# GR.net
KiCad netlist of a schematic drawn in Altium Designer
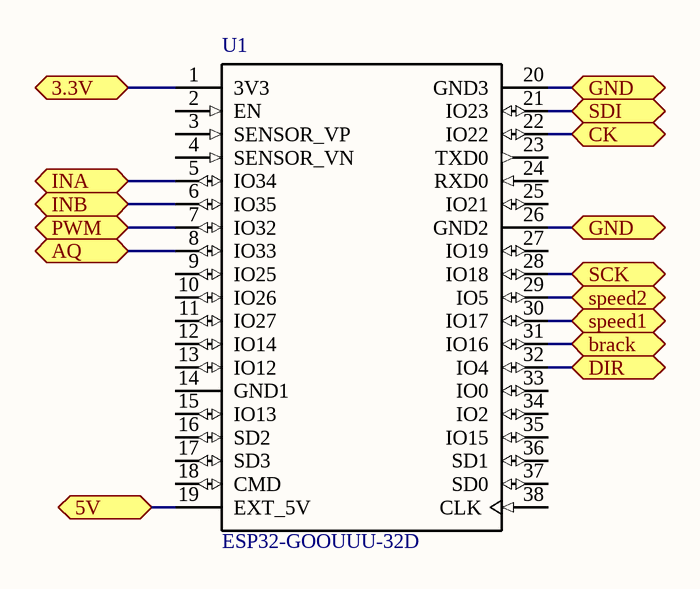
[diagram p0: GR.SchDoc]

(export (version "E")
  (design (tool "Eeschema 10.0.6"))
  (components
    (comp (ref "U1")
      (value "ESP32-GOOUUU-32D")
      (footprint "ESP32-GOOUUU-32D")
      (description "Eval Board For Esp-Wroom-32")
      (fields (field (name "MP") "ESP32-DEVKITC-32D") (field (name "MF") "Espressif Systems"))
      (libsource (lib "ESP32-GOOUUU-32D") (part "ESP32-GOOUUU-32D"))
    )
  )
  (nets
    (net (code "1") (name "/3.3V") (class "Default")
      (node (ref "U1") (pin "1") (pinfunction "3V3_1") (pintype "power_in"))
    )
    (net (code "2") (name "/5V") (class "Default")
      (node (ref "U1") (pin "19") (pinfunction "EXT_5V_19") (pintype "power_in"))
    )
    (net (code "3") (name "/AQ") (class "Default")
      (node (ref "U1") (pin "8") (pinfunction "IO33_8") (pintype "bidirectional"))
    )
    (net (code "4") (name "/CK") (class "Default")
      (node (ref "U1") (pin "22") (pinfunction "IO22_22") (pintype "bidirectional"))
    )
    (net (code "5") (name "/DIR") (class "Default")
      (node (ref "U1") (pin "32") (pinfunction "IO4_32") (pintype "bidirectional"))
    )
    (net (code "6") (name "/GND") (class "Default")
      (node (ref "U1") (pin "20") (pinfunction "GND3_20") (pintype "power_in"))
      (node (ref "U1") (pin "26") (pinfunction "GND2_26") (pintype "power_in"))
    )
    (net (code "7") (name "/INA") (class "Default")
      (node (ref "U1") (pin "5") (pinfunction "IO34_5") (pintype "bidirectional"))
    )
    (net (code "8") (name "/INB") (class "Default")
      (node (ref "U1") (pin "6") (pinfunction "IO35_6") (pintype "bidirectional"))
    )
    (net (code "9") (name "/PWM") (class "Default")
      (node (ref "U1") (pin "7") (pinfunction "IO32_7") (pintype "bidirectional"))
    )
    (net (code "10") (name "/SCK") (class "Default")
      (node (ref "U1") (pin "28") (pinfunction "IO18_28") (pintype "bidirectional"))
    )
    (net (code "11") (name "/SDI") (class "Default")
      (node (ref "U1") (pin "21") (pinfunction "IO23_21") (pintype "bidirectional"))
    )
    (net (code "12") (name "/brack") (class "Default")
      (node (ref "U1") (pin "31") (pinfunction "IO16_31") (pintype "bidirectional"))
    )
    (net (code "13") (name "/speed1") (class "Default")
      (node (ref "U1") (pin "30") (pinfunction "IO17_30") (pintype "bidirectional"))
    )
    (net (code "14") (name "/speed2") (class "Default")
      (node (ref "U1") (pin "29") (pinfunction "IO5_29") (pintype "bidirectional"))
    )
    (net (code "15") (name "unconnected-(U1-CLK-Pad38)") (class "Default")
      (node (ref "U1") (pin "38") (pinfunction "CLK_38") (pintype "input"))
    )
    (net (code "16") (name "unconnected-(U1-CMD-Pad18)") (class "Default")
      (node (ref "U1") (pin "18") (pinfunction "CMD_18") (pintype "bidirectional"))
    )
    (net (code "17") (name "unconnected-(U1-EN-Pad2)") (class "Default")
      (node (ref "U1") (pin "2") (pinfunction "EN_2") (pintype "input"))
    )
    (net (code "18") (name "unconnected-(U1-GND1-Pad14)") (class "Default")
      (node (ref "U1") (pin "14") (pinfunction "GND1_14") (pintype "power_in"))
    )
    (net (code "19") (name "unconnected-(U1-IO0-Pad33)") (class "Default")
      (node (ref "U1") (pin "33") (pinfunction "IO0_33") (pintype "bidirectional"))
    )
    (net (code "20") (name "unconnected-(U1-IO2-Pad34)") (class "Default")
      (node (ref "U1") (pin "34") (pinfunction "IO2_34") (pintype "bidirectional"))
    )
    (net (code "21") (name "unconnected-(U1-IO12-Pad13)") (class "Default")
      (node (ref "U1") (pin "13") (pinfunction "IO12_13") (pintype "bidirectional"))
    )
    (net (code "22") (name "unconnected-(U1-IO13-Pad15)") (class "Default")
      (node (ref "U1") (pin "15") (pinfunction "IO13_15") (pintype "bidirectional"))
    )
    (net (code "23") (name "unconnected-(U1-IO14-Pad12)") (class "Default")
      (node (ref "U1") (pin "12") (pinfunction "IO14_12") (pintype "bidirectional"))
    )
    (net (code "24") (name "unconnected-(U1-IO15-Pad35)") (class "Default")
      (node (ref "U1") (pin "35") (pinfunction "IO15_35") (pintype "bidirectional"))
    )
    (net (code "25") (name "unconnected-(U1-IO19-Pad27)") (class "Default")
      (node (ref "U1") (pin "27") (pinfunction "IO19_27") (pintype "bidirectional"))
    )
    (net (code "26") (name "unconnected-(U1-IO21-Pad25)") (class "Default")
      (node (ref "U1") (pin "25") (pinfunction "IO21_25") (pintype "bidirectional"))
    )
    (net (code "27") (name "unconnected-(U1-IO25-Pad9)") (class "Default")
      (node (ref "U1") (pin "9") (pinfunction "IO25_9") (pintype "bidirectional"))
    )
    (net (code "28") (name "unconnected-(U1-IO26-Pad10)") (class "Default")
      (node (ref "U1") (pin "10") (pinfunction "IO26_10") (pintype "bidirectional"))
    )
    (net (code "29") (name "unconnected-(U1-IO27-Pad11)") (class "Default")
      (node (ref "U1") (pin "11") (pinfunction "IO27_11") (pintype "bidirectional"))
    )
    (net (code "30") (name "unconnected-(U1-RXD0-Pad24)") (class "Default")
      (node (ref "U1") (pin "24") (pinfunction "RXD0_24") (pintype "input"))
    )
    (net (code "31") (name "unconnected-(U1-SD0-Pad37)") (class "Default")
      (node (ref "U1") (pin "37") (pinfunction "SD0_37") (pintype "bidirectional"))
    )
    (net (code "32") (name "unconnected-(U1-SD1-Pad36)") (class "Default")
      (node (ref "U1") (pin "36") (pinfunction "SD1_36") (pintype "bidirectional"))
    )
    (net (code "33") (name "unconnected-(U1-SD2-Pad16)") (class "Default")
      (node (ref "U1") (pin "16") (pinfunction "SD2_16") (pintype "bidirectional"))
    )
    (net (code "34") (name "unconnected-(U1-SD3-Pad17)") (class "Default")
      (node (ref "U1") (pin "17") (pinfunction "SD3_17") (pintype "bidirectional"))
    )
    (net (code "35") (name "unconnected-(U1-SENSOR_VN-Pad4)") (class "Default")
      (node (ref "U1") (pin "4") (pinfunction "SENSOR_VN_4") (pintype "input"))
    )
    (net (code "36") (name "unconnected-(U1-SENSOR_VP-Pad3)") (class "Default")
      (node (ref "U1") (pin "3") (pinfunction "SENSOR_VP_3") (pintype "input"))
    )
    (net (code "37") (name "unconnected-(U1-TXD0-Pad23)") (class "Default")
      (node (ref "U1") (pin "23") (pinfunction "TXD0_23") (pintype "output"))
    )
  )
)
